# 150107_AriloTX_REV2_2_0_868MHZ_td.net
KiCad netlist of a schematic drawn in EAGLE
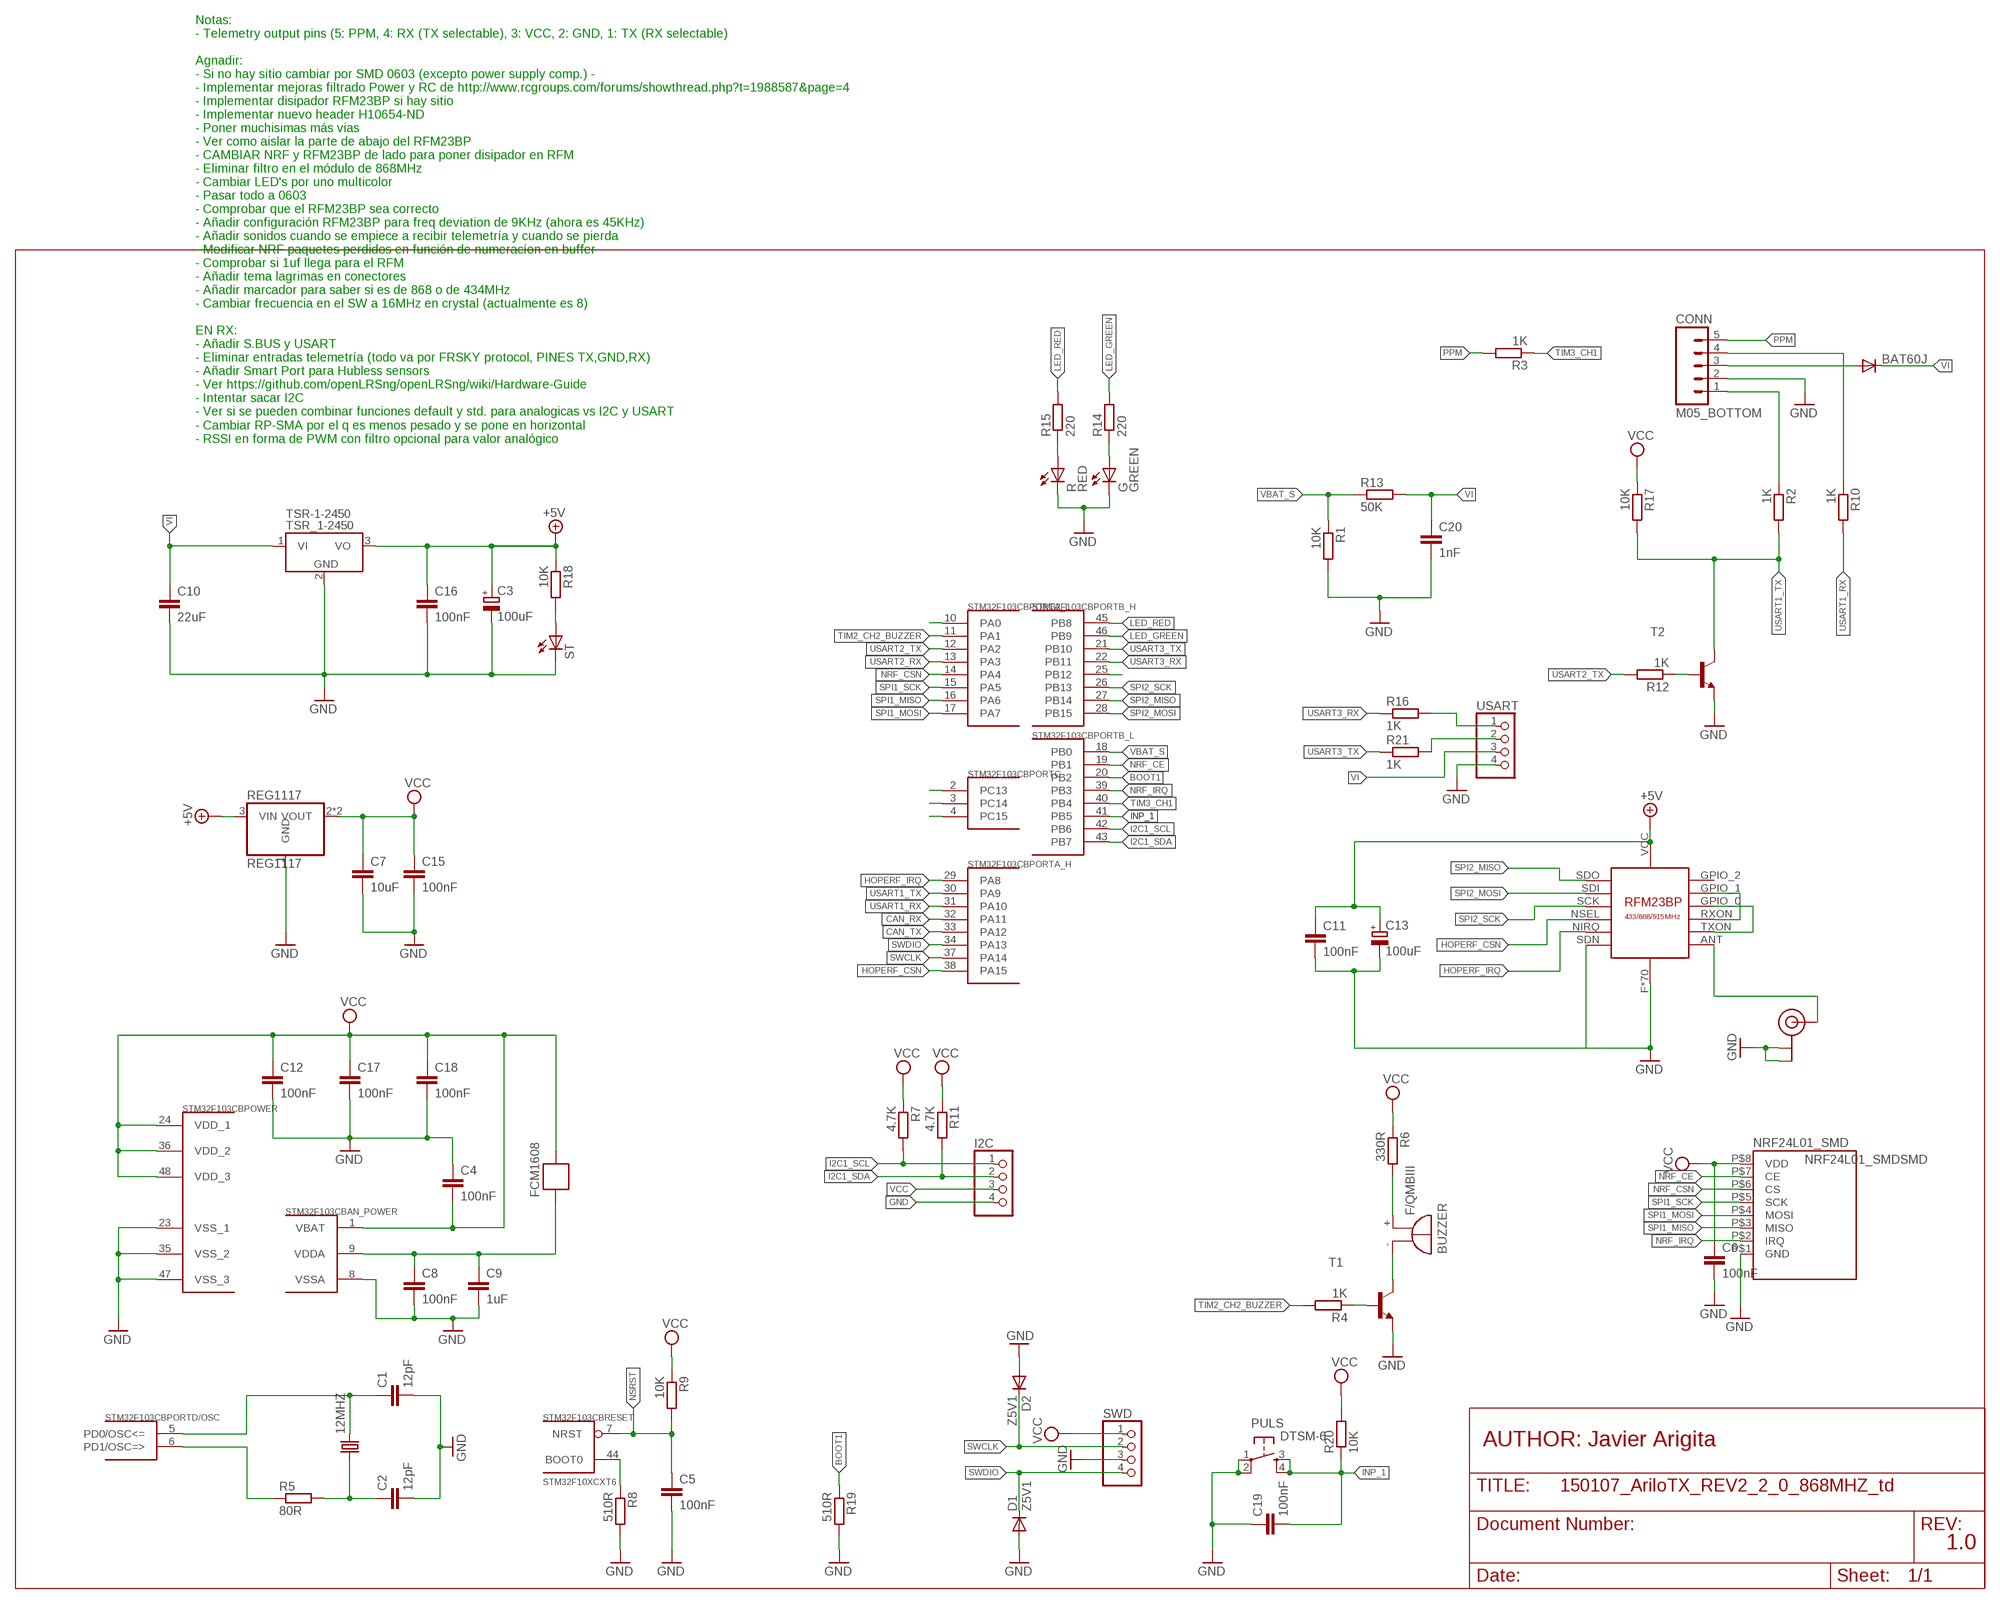
[diagram p0: schematic, sheet 1]

(export (version "E")
  (design (tool "Eeschema 10.0.6"))
  (components
    (comp (ref "12MHZ")
      (value "CRYSTAL5X3")
      (footprint "eagle-import:CRYSTAL-SMD-5X3")
      (libsource (lib "eagle-import") (part "CRYSTAL5X3"))
    )
    (comp (ref "BAT60J")
      (value "DIODE-SOD323-R")
      (footprint "eagle-import:SOD323-R")
      (libsource (lib "eagle-import") (part "DIODE-SOD323-R"))
    )
    (comp (ref "BUZZER")
      (value "F/QMBIII")
      (footprint "eagle-import:F_QMBIII")
      (libsource (lib "eagle-import") (part "F/QMBIII"))
    )
    (comp (ref "C1")
      (value "12pF")
      (footprint "eagle-import:C0603")
      (libsource (lib "eagle-import") (part "C-EUC0603"))
    )
    (comp (ref "C2")
      (value "12pF")
      (footprint "eagle-import:C0603")
      (libsource (lib "eagle-import") (part "C-EUC0603"))
    )
    (comp (ref "C3")
      (value "100uF")
      (footprint "eagle-import:SMC_B")
      (libsource (lib "eagle-import") (part "CPOL-EUSMCB"))
    )
    (comp (ref "C4")
      (value "100nF")
      (footprint "eagle-import:C0603")
      (libsource (lib "eagle-import") (part "C-EUC0603"))
    )
    (comp (ref "C5")
      (value "100nF")
      (footprint "eagle-import:C0603")
      (libsource (lib "eagle-import") (part "C-EUC0603"))
    )
    (comp (ref "C6")
      (value "100nF")
      (footprint "eagle-import:C0603")
      (libsource (lib "eagle-import") (part "C-EUC0603"))
    )
    (comp (ref "C7")
      (value "10uF")
      (footprint "eagle-import:C0805")
      (libsource (lib "eagle-import") (part "C-EUC0805"))
    )
    (comp (ref "C8")
      (value "100nF")
      (footprint "eagle-import:C0603")
      (libsource (lib "eagle-import") (part "C-EUC0603"))
    )
    (comp (ref "C9")
      (value "1uF")
      (footprint "eagle-import:C0603")
      (libsource (lib "eagle-import") (part "C-EUC0603"))
    )
    (comp (ref "C10")
      (value "22uF")
      (footprint "eagle-import:C3216")
      (libsource (lib "eagle-import") (part "resistor_C-EUC3216"))
    )
    (comp (ref "C11")
      (value "100nF")
      (footprint "eagle-import:C0603")
      (libsource (lib "eagle-import") (part "C-EUC0603"))
    )
    (comp (ref "C12")
      (value "100nF")
      (footprint "eagle-import:C0603")
      (libsource (lib "eagle-import") (part "C-EUC0603"))
    )
    (comp (ref "C13")
      (value "100uF")
      (footprint "eagle-import:SMC_B")
      (libsource (lib "eagle-import") (part "CPOL-EUSMCB"))
    )
    (comp (ref "C15")
      (value "100nF")
      (footprint "eagle-import:C0603")
      (libsource (lib "eagle-import") (part "C-EUC0603"))
    )
    (comp (ref "C16")
      (value "100nF")
      (footprint "eagle-import:C0603")
      (libsource (lib "eagle-import") (part "C-EUC0603"))
    )
    (comp (ref "C17")
      (value "100nF")
      (footprint "eagle-import:C0603")
      (libsource (lib "eagle-import") (part "C-EUC0603"))
    )
    (comp (ref "C18")
      (value "100nF")
      (footprint "eagle-import:C0603")
      (libsource (lib "eagle-import") (part "C-EUC0603"))
    )
    (comp (ref "C19")
      (value "100nF")
      (footprint "eagle-import:C0603")
      (libsource (lib "eagle-import") (part "C-EUC0603"))
    )
    (comp (ref "C20")
      (value "1nF")
      (footprint "eagle-import:C0603")
      (libsource (lib "eagle-import") (part "C-EUC0603"))
    )
    (comp (ref "CONN")
      (value "M05_BOTTOM")
      (footprint "eagle-import:M05_BOTTOM")
      (libsource (lib "eagle-import") (part "M05_BOTTOM"))
    )
    (comp (ref "D1")
      (value "Z5V1")
      (footprint "eagle-import:SOD323-R")
      (libsource (lib "eagle-import") (part "DIODE-SOD323-R"))
    )
    (comp (ref "D2")
      (value "Z5V1")
      (footprint "eagle-import:SOD323-R")
      (libsource (lib "eagle-import") (part "DIODE-SOD323-R"))
    )
    (comp (ref "FCM1608")
      (value "FERRITE-BEAD")
      (footprint "eagle-import:R0603")
      (libsource (lib "eagle-import") (part "FERRITE-BEAD"))
    )
    (comp (ref "G")
      (value "GREEN")
      (footprint "eagle-import:CHIP-LED0603")
      (libsource (lib "eagle-import") (part "LEDCHIP-LED0603"))
    )
    (comp (ref "I2C")
      (value "PINHD-1X4")
      (footprint "eagle-import:1X04")
      (libsource (lib "eagle-import") (part "PINHD-1X4"))
    )
    (comp (ref "NRF24L01_SMD")
      (value "NRF24L01_SMDSMD")
      (footprint "eagle-import:NRF24L01_SMD")
      (libsource (lib "eagle-import") (part "NRF24L01_SMDSMD"))
    )
    (comp (ref "PULS")
      (value "DTSM-6")
      (footprint "eagle-import:DTSM-6")
      (libsource (lib "eagle-import") (part "DTSM-6"))
    )
    (comp (ref "R")
      (value "RED")
      (footprint "eagle-import:CHIP-LED0603")
      (libsource (lib "eagle-import") (part "LEDCHIP-LED0603"))
    )
    (comp (ref "R1")
      (value "10K")
      (footprint "eagle-import:R0603")
      (libsource (lib "eagle-import") (part "R-EU_R0603"))
    )
    (comp (ref "R2")
      (value "1K")
      (footprint "eagle-import:R0603")
      (libsource (lib "eagle-import") (part "R-EU_R0603"))
    )
    (comp (ref "R3")
      (value "1K")
      (footprint "eagle-import:R0603")
      (libsource (lib "eagle-import") (part "R-EU_R0603"))
    )
    (comp (ref "R4")
      (value "1K")
      (footprint "eagle-import:R0603")
      (libsource (lib "eagle-import") (part "R-EU_R0603"))
    )
    (comp (ref "R5")
      (value "80R")
      (footprint "eagle-import:R0603")
      (libsource (lib "eagle-import") (part "R-EU_R0603"))
    )
    (comp (ref "R6")
      (value "330R")
      (footprint "eagle-import:R0603")
      (libsource (lib "eagle-import") (part "R-EU_R0603"))
    )
    (comp (ref "R7")
      (value "4.7K")
      (footprint "eagle-import:R0603")
      (libsource (lib "eagle-import") (part "R-EU_R0603"))
    )
    (comp (ref "R8")
      (value "510R")
      (footprint "eagle-import:R0603")
      (libsource (lib "eagle-import") (part "R-EU_R0603"))
    )
    (comp (ref "R9")
      (value "10K")
      (footprint "eagle-import:R0603")
      (libsource (lib "eagle-import") (part "R-EU_R0603"))
    )
    (comp (ref "R10")
      (value "1K")
      (footprint "eagle-import:R0603")
      (libsource (lib "eagle-import") (part "R-EU_R0603"))
    )
    (comp (ref "R11")
      (value "4.7K")
      (footprint "eagle-import:R0603")
      (libsource (lib "eagle-import") (part "R-EU_R0603"))
    )
    (comp (ref "R12")
      (value "1K")
      (footprint "eagle-import:R0603")
      (libsource (lib "eagle-import") (part "R-EU_R0603"))
    )
    (comp (ref "R13")
      (value "50K")
      (footprint "eagle-import:R0603")
      (libsource (lib "eagle-import") (part "R-EU_R0603"))
    )
    (comp (ref "R14")
      (value "220")
      (footprint "eagle-import:R0603")
      (libsource (lib "eagle-import") (part "R-EU_R0603"))
    )
    (comp (ref "R15")
      (value "220")
      (footprint "eagle-import:R0603")
      (libsource (lib "eagle-import") (part "R-EU_R0603"))
    )
    (comp (ref "R16")
      (value "1K")
      (footprint "eagle-import:R0603")
      (libsource (lib "eagle-import") (part "R-EU_R0603"))
    )
    (comp (ref "R17")
      (value "10K")
      (footprint "eagle-import:R0603")
      (libsource (lib "eagle-import") (part "R-EU_R0603"))
    )
    (comp (ref "R18")
      (value "10K")
      (footprint "eagle-import:R0603")
      (libsource (lib "eagle-import") (part "R-EU_R0603"))
    )
    (comp (ref "R19")
      (value "510R")
      (footprint "eagle-import:R0603")
      (libsource (lib "eagle-import") (part "R-EU_R0603"))
    )
    (comp (ref "R20")
      (value "10K")
      (footprint "eagle-import:R0603")
      (libsource (lib "eagle-import") (part "R-EU_R0603"))
    )
    (comp (ref "R21")
      (value "1K")
      (footprint "eagle-import:R0603")
      (libsource (lib "eagle-import") (part "R-EU_R0603"))
    )
    (comp (ref "REG1117")
      (value "REG1117")
      (footprint "eagle-import:SOT223")
      (libsource (lib "eagle-import") (part "REG1117"))
    )
    (comp (ref "ST")
      (value "LEDCHIP-LED0603")
      (footprint "eagle-import:CHIP-LED0603")
      (libsource (lib "eagle-import") (part "LEDCHIP-LED0603"))
    )
    (comp (ref "STM32F103CB")
      (value "STM32F10XCXT6")
      (footprint "eagle-import:TQFP48")
      (libsource (lib "eagle-import") (part "STM32F10XCXT6"))
    )
    (comp (ref "SWD")
      (value "PINHD-1X4")
      (footprint "eagle-import:1X04")
      (libsource (lib "eagle-import") (part "PINHD-1X4"))
    )
    (comp (ref "T1")
      (value "BC848-NPN-SOT23-BEC")
      (footprint "eagle-import:SOT23-BEC")
      (libsource (lib "eagle-import") (part "-NPN-SOT23-BECBC848"))
    )
    (comp (ref "T2")
      (value "BC848-NPN-SOT23-BEC")
      (footprint "eagle-import:SOT23-BEC")
      (libsource (lib "eagle-import") (part "-NPN-SOT23-BECBC848"))
    )
    (comp (ref "TSR-1-2450")
      (value "TSR_1-2450")
      (footprint "eagle-import:TSR-1")
      (libsource (lib "eagle-import") (part "TSR_1-2450"))
    )
    (comp (ref "U$1")
      (value "RFM23BP")
      (footprint "eagle-import:RFM23BP")
      (libsource (lib "eagle-import") (part "RFM23BP"))
    )
    (comp (ref "U.FL")
      (value "U.FL")
      (footprint "eagle-import:U.FL")
      (libsource (lib "eagle-import") (part "U.FL"))
    )
    (comp (ref "USART")
      (value "PINHD-1X4")
      (footprint "eagle-import:1X04")
      (libsource (lib "eagle-import") (part "PINHD-1X4"))
    )
  )
  (nets
    (net (code "1") (name "+5V") (class "Default")
      (node (ref "C11") (pin "1") (pinfunction "1_1") (pintype "passive"))
      (node (ref "C13") (pin "+") (pinfunction "+_+") (pintype "passive"))
      (node (ref "C16") (pin "1") (pinfunction "1_1") (pintype "passive"))
      (node (ref "C3") (pin "+") (pinfunction "+_+") (pintype "passive"))
      (node (ref "R18") (pin "1") (pinfunction "1_1") (pintype "passive"))
      (node (ref "REG1117") (pin "3") (pinfunction "VIN_3") (pintype "input"))
      (node (ref "TSR-1-2450") (pin "3") (pinfunction "VO_3") (pintype "power_in"))
      (node (ref "U$1") (pin "VCC") (pinfunction "VCC_VCC") (pintype "power_in"))
    )
    (net (code "2") (name "BOOT1") (class "Default")
      (node (ref "R19") (pin "1") (pinfunction "1_1") (pintype "passive"))
      (node (ref "STM32F103CB") (pin "20") (pinfunction "PB2_20") (pintype "bidirectional"))
    )
    (net (code "3") (name "CAN_RX") (class "Default")
      (node (ref "STM32F103CB") (pin "32") (pinfunction "PA11_32") (pintype "bidirectional"))
    )
    (net (code "4") (name "CAN_TX") (class "Default")
      (node (ref "STM32F103CB") (pin "33") (pinfunction "PA12_33") (pintype "bidirectional"))
    )
    (net (code "5") (name "GND") (class "Default")
      (node (ref "C1") (pin "2") (pinfunction "2_2") (pintype "passive"))
      (node (ref "C10") (pin "2") (pinfunction "2_2") (pintype "passive"))
      (node (ref "C11") (pin "2") (pinfunction "2_2") (pintype "passive"))
      (node (ref "C12") (pin "2") (pinfunction "2_2") (pintype "passive"))
      (node (ref "C13") (pin "-") (pinfunction "-_-") (pintype "passive"))
      (node (ref "C15") (pin "2") (pinfunction "2_2") (pintype "passive"))
      (node (ref "C16") (pin "2") (pinfunction "2_2") (pintype "passive"))
      (node (ref "C17") (pin "2") (pinfunction "2_2") (pintype "passive"))
      (node (ref "C18") (pin "2") (pinfunction "2_2") (pintype "passive"))
      (node (ref "C19") (pin "1") (pinfunction "1_1") (pintype "passive"))
      (node (ref "C2") (pin "2") (pinfunction "2_2") (pintype "passive"))
      (node (ref "C20") (pin "2") (pinfunction "2_2") (pintype "passive"))
      (node (ref "C3") (pin "-") (pinfunction "-_-") (pintype "passive"))
      (node (ref "C4") (pin "1") (pinfunction "1_1") (pintype "passive"))
      (node (ref "C5") (pin "2") (pinfunction "2_2") (pintype "passive"))
      (node (ref "C6") (pin "2") (pinfunction "2_2") (pintype "passive"))
      (node (ref "C7") (pin "2") (pinfunction "2_2") (pintype "passive"))
      (node (ref "C8") (pin "2") (pinfunction "2_2") (pintype "passive"))
      (node (ref "C9") (pin "2") (pinfunction "2_2") (pintype "passive"))
      (node (ref "CONN") (pin "2") (pinfunction "2_2") (pintype "passive"))
      (node (ref "D1") (pin "A") (pinfunction "A_A") (pintype "passive"))
      (node (ref "D2") (pin "A") (pinfunction "A_A") (pintype "passive"))
      (node (ref "G") (pin "C") (pinfunction "C_C") (pintype "passive"))
      (node (ref "I2C") (pin "4") (pinfunction "4_4") (pintype "passive"))
      (node (ref "NRF24L01_SMD") (pin "P$1") (pinfunction "GND_P$1") (pintype "power_in"))
      (node (ref "PULS") (pin "1") (pinfunction "1_1") (pintype "passive"))
      (node (ref "PULS") (pin "2") (pinfunction "2_2") (pintype "passive"))
      (node (ref "R") (pin "C") (pinfunction "C_C") (pintype "passive"))
      (node (ref "R1") (pin "2") (pinfunction "2_2") (pintype "passive"))
      (node (ref "R19") (pin "2") (pinfunction "2_2") (pintype "passive"))
      (node (ref "R8") (pin "2") (pinfunction "2_2") (pintype "passive"))
      (node (ref "REG1117") (pin "1") (pinfunction "GND_1") (pintype "power_in"))
      (node (ref "ST") (pin "C") (pinfunction "C_C") (pintype "passive"))
      (node (ref "STM32F103CB") (pin "23") (pinfunction "VSS_1_23") (pintype "power_in"))
      (node (ref "STM32F103CB") (pin "35") (pinfunction "VSS_2_35") (pintype "power_in"))
      (node (ref "STM32F103CB") (pin "47") (pinfunction "VSS_3_47") (pintype "power_in"))
      (node (ref "STM32F103CB") (pin "8") (pinfunction "VSSA_8") (pintype "power_in"))
      (node (ref "SWD") (pin "3") (pinfunction "3_3") (pintype "passive"))
      (node (ref "T1") (pin "E") (pinfunction "E_E") (pintype "passive"))
      (node (ref "T2") (pin "E") (pinfunction "E_E") (pintype "passive"))
      (node (ref "TSR-1-2450") (pin "2") (pinfunction "GND_2") (pintype "power_in"))
      (node (ref "U$1") (pin "F") (pinfunction "GND_F") (pintype "power_in"))
      (node (ref "U$1") (pin "F1") (pinfunction "GND_F1") (pintype "power_in"))
      (node (ref "U$1") (pin "F10") (pinfunction "GND_F10") (pintype "power_in"))
      (node (ref "U$1") (pin "F11") (pinfunction "GND_F11") (pintype "power_in"))
      (node (ref "U$1") (pin "F12") (pinfunction "GND_F12") (pintype "power_in"))
      (node (ref "U$1") (pin "F13") (pinfunction "GND_F13") (pintype "power_in"))
      (node (ref "U$1") (pin "F14") (pinfunction "GND_F14") (pintype "power_in"))
      (node (ref "U$1") (pin "F15") (pinfunction "GND_F15") (pintype "power_in"))
      (node (ref "U$1") (pin "F16") (pinfunction "GND_F16") (pintype "power_in"))
      (node (ref "U$1") (pin "F17") (pinfunction "GND_F17") (pintype "power_in"))
      (node (ref "U$1") (pin "F18") (pinfunction "GND_F18") (pintype "power_in"))
      (node (ref "U$1") (pin "F19") (pinfunction "GND_F19") (pintype "power_in"))
      (node (ref "U$1") (pin "F2") (pinfunction "GND_F2") (pintype "power_in"))
      (node (ref "U$1") (pin "F20") (pinfunction "GND_F20") (pintype "power_in"))
      (node (ref "U$1") (pin "F21") (pinfunction "GND_F21") (pintype "power_in"))
      (node (ref "U$1") (pin "F22") (pinfunction "GND_F22") (pintype "power_in"))
      (node (ref "U$1") (pin "F23") (pinfunction "GND_F23") (pintype "power_in"))
      (node (ref "U$1") (pin "F24") (pinfunction "GND_F24") (pintype "power_in"))
      (node (ref "U$1") (pin "F25") (pinfunction "GND_F25") (pintype "power_in"))
      (node (ref "U$1") (pin "F26") (pinfunction "GND_F26") (pintype "power_in"))
      (node (ref "U$1") (pin "F27") (pinfunction "GND_F27") (pintype "power_in"))
      (node (ref "U$1") (pin "F28") (pinfunction "GND_F28") (pintype "power_in"))
      (node (ref "U$1") (pin "F29") (pinfunction "GND_F29") (pintype "power_in"))
      (node (ref "U$1") (pin "F3") (pinfunction "GND_F3") (pintype "power_in"))
      (node (ref "U$1") (pin "F30") (pinfunction "GND_F30") (pintype "power_in"))
      (node (ref "U$1") (pin "F31") (pinfunction "GND_F31") (pintype "power_in"))
      (node (ref "U$1") (pin "F32") (pinfunction "GND_F32") (pintype "power_in"))
      (node (ref "U$1") (pin "F33") (pinfunction "GND_F33") (pintype "power_in"))
      (node (ref "U$1") (pin "F34") (pinfunction "GND_F34") (pintype "power_in"))
      (node (ref "U$1") (pin "F35") (pinfunction "GND_F35") (pintype "power_in"))
      (node (ref "U$1") (pin "F36") (pinfunction "GND_F36") (pintype "power_in"))
      (node (ref "U$1") (pin "F37") (pinfunction "GND_F37") (pintype "power_in"))
      (node (ref "U$1") (pin "F38") (pinfunction "GND_F38") (pintype "power_in"))
      (node (ref "U$1") (pin "F39") (pinfunction "GND_F39") (pintype "power_in"))
      (node (ref "U$1") (pin "F4") (pinfunction "GND_F4") (pintype "power_in"))
      (node (ref "U$1") (pin "F40") (pinfunction "GND_F40") (pintype "power_in"))
      (node (ref "U$1") (pin "F41") (pinfunction "GND_F41") (pintype "power_in"))
      (node (ref "U$1") (pin "F42") (pinfunction "GND_F42") (pintype "power_in"))
      (node (ref "U$1") (pin "F43") (pinfunction "GND_F43") (pintype "power_in"))
      (node (ref "U$1") (pin "F44") (pinfunction "GND_F44") (pintype "power_in"))
      (node (ref "U$1") (pin "F45") (pinfunction "GND_F45") (pintype "power_in"))
      (node (ref "U$1") (pin "F46") (pinfunction "GND_F46") (pintype "power_in"))
      (node (ref "U$1") (pin "F47") (pinfunction "GND_F47") (pintype "power_in"))
      (node (ref "U$1") (pin "F48") (pinfunction "GND_F48") (pintype "power_in"))
      (node (ref "U$1") (pin "F49") (pinfunction "GND_F49") (pintype "power_in"))
      (node (ref "U$1") (pin "F5") (pinfunction "GND_F5") (pintype "power_in"))
      (node (ref "U$1") (pin "F50") (pinfunction "GND_F50") (pintype "power_in"))
      (node (ref "U$1") (pin "F51") (pinfunction "GND_F51") (pintype "power_in"))
      (node (ref "U$1") (pin "F52") (pinfunction "GND_F52") (pintype "power_in"))
      (node (ref "U$1") (pin "F53") (pinfunction "GND_F53") (pintype "power_in"))
      (node (ref "U$1") (pin "F54") (pinfunction "GND_F54") (pintype "power_in"))
      (node (ref "U$1") (pin "F55") (pinfunction "GND_F55") (pintype "power_in"))
      (node (ref "U$1") (pin "F56") (pinfunction "GND_F56") (pintype "power_in"))
      (node (ref "U$1") (pin "F57") (pinfunction "GND_F57") (pintype "power_in"))
      (node (ref "U$1") (pin "F58") (pinfunction "GND_F58") (pintype "power_in"))
      (node (ref "U$1") (pin "F59") (pinfunction "GND_F59") (pintype "power_in"))
      (node (ref "U$1") (pin "F6") (pinfunction "GND_F6") (pintype "power_in"))
      (node (ref "U$1") (pin "F60") (pinfunction "GND_F60") (pintype "power_in"))
      (node (ref "U$1") (pin "F61") (pinfunction "GND_F61") (pintype "power_in"))
      (node (ref "U$1") (pin "F62") (pinfunction "GND_F62") (pintype "power_in"))
      (node (ref "U$1") (pin "F63") (pinfunction "GND_F63") (pintype "power_in"))
      (node (ref "U$1") (pin "F64") (pinfunction "GND_F64") (pintype "power_in"))
      (node (ref "U$1") (pin "F65") (pinfunction "GND_F65") (pintype "power_in"))
      (node (ref "U$1") (pin "F7") (pinfunction "GND_F7") (pintype "power_in"))
      (node (ref "U$1") (pin "F8") (pinfunction "GND_F8") (pintype "power_in"))
      (node (ref "U$1") (pin "F9") (pinfunction "GND_F9") (pintype "power_in"))
      (node (ref "U$1") (pin "GND1") (pinfunction "GND_GND1") (pintype "power_in"))
      (node (ref "U$1") (pin "GND2") (pinfunction "GND_GND2") (pintype "power_in"))
      (node (ref "U$1") (pin "GND3") (pinfunction "GND_GND3") (pintype "power_in"))
      (node (ref "U$1") (pin "GND_HEAT") (pinfunction "GND_GND_HEAT") (pintype "power_in"))
      (node (ref "U$1") (pin "SDN") (pinfunction "SDN_SDN") (pintype "bidirectional"))
      (node (ref "U.FL") (pin "P$1") (pinfunction "GND_P$1") (pintype "bidirectional"))
      (node (ref "U.FL") (pin "P$2") (pinfunction "GND_P$2") (pintype "bidirectional"))
      (node (ref "USART") (pin "4") (pinfunction "4_4") (pintype "passive"))
    )
    (net (code "6") (name "HOPERF_CSN") (class "Default")
      (node (ref "STM32F103CB") (pin "38") (pinfunction "PA15_38") (pintype "bidirectional"))
      (node (ref "U$1") (pin "NSEL") (pinfunction "NSEL_NSEL") (pintype "bidirectional"))
    )
    (net (code "7") (name "HOPERF_IRQ") (class "Default")
      (node (ref "STM32F103CB") (pin "29") (pinfunction "PA8_29") (pintype "bidirectional"))
      (node (ref "U$1") (pin "NIRQ") (pinfunction "NIRQ_NIRQ") (pintype "bidirectional"))
    )
    (net (code "8") (name "I2C1_SCL") (class "Default")
      (node (ref "I2C") (pin "1") (pinfunction "1_1") (pintype "passive"))
      (node (ref "R7") (pin "2") (pinfunction "2_2") (pintype "passive"))
      (node (ref "STM32F103CB") (pin "42") (pinfunction "PB6_42") (pintype "bidirectional"))
    )
    (net (code "9") (name "I2C1_SDA") (class "Default")
      (node (ref "I2C") (pin "2") (pinfunction "2_2") (pintype "passive"))
      (node (ref "R11") (pin "2") (pinfunction "2_2") (pintype "passive"))
      (node (ref "STM32F103CB") (pin "43") (pinfunction "PB7_43") (pintype "bidirectional"))
    )
    (net (code "10") (name "INP_1") (class "Default")
      (node (ref "C19") (pin "2") (pinfunction "2_2") (pintype "passive"))
      (node (ref "PULS") (pin "3") (pinfunction "3_3") (pintype "passive"))
      (node (ref "PULS") (pin "4") (pinfunction "4_4") (pintype "passive"))
      (node (ref "R20") (pin "1") (pinfunction "1_1") (pintype "passive"))
      (node (ref "STM32F103CB") (pin "41") (pinfunction "PB5_41") (pintype "bidirectional"))
    )
    (net (code "11") (name "LED_GREEN") (class "Default")
      (node (ref "R14") (pin "2") (pinfunction "2_2") (pintype "passive"))
      (node (ref "STM32F103CB") (pin "46") (pinfunction "PB9_46") (pintype "bidirectional"))
    )
    (net (code "12") (name "LED_RED") (class "Default")
      (node (ref "R15") (pin "2") (pinfunction "2_2") (pintype "passive"))
      (node (ref "STM32F103CB") (pin "45") (pinfunction "PB8_45") (pintype "bidirectional"))
    )
    (net (code "13") (name "NRF_CE") (class "Default")
      (node (ref "NRF24L01_SMD") (pin "P$7") (pinfunction "CE_P$7") (pintype "input"))
      (node (ref "STM32F103CB") (pin "19") (pinfunction "PB1_19") (pintype "bidirectional"))
    )
    (net (code "14") (name "NRF_CSN") (class "Default")
      (node (ref "NRF24L01_SMD") (pin "P$6") (pinfunction "CS_P$6") (pintype "input"))
      (node (ref "STM32F103CB") (pin "14") (pinfunction "PA4_14") (pintype "bidirectional"))
    )
    (net (code "15") (name "NRF_IRQ") (class "Default")
      (node (ref "NRF24L01_SMD") (pin "P$2") (pinfunction "IRQ_P$2") (pintype "output"))
      (node (ref "STM32F103CB") (pin "39") (pinfunction "PB3_39") (pintype "bidirectional"))
    )
    (net (code "16") (name "NSRST") (class "Default")
      (node (ref "C5") (pin "1") (pinfunction "1_1") (pintype "passive"))
      (node (ref "R9") (pin "2") (pinfunction "2_2") (pintype "passive"))
      (node (ref "STM32F103CB") (pin "7") (pinfunction "NRST_7") (pintype "input"))
    )
    (net (code "17") (name "Net-(12MHZ-2)") (class "Default")
      (node (ref "12MHZ") (pin "3") (pinfunction "2_3") (pintype "passive"))
      (node (ref "C1") (pin "1") (pinfunction "1_1") (pintype "passive"))
      (node (ref "STM32F103CB") (pin "5") (pinfunction "PD0/OSC<=_5") (pintype "bidirectional"))
    )
    (net (code "18") (name "Net-(12MHZ-Pad1)") (class "Default")
      (node (ref "12MHZ") (pin "1") (pinfunction "1_1") (pintype "passive"))
      (node (ref "C2") (pin "1") (pinfunction "1_1") (pintype "passive"))
      (node (ref "R5") (pin "2") (pinfunction "2_2") (pintype "passive"))
    )
    (net (code "19") (name "Net-(BAT60J-PadA)") (class "Default")
      (node (ref "BAT60J") (pin "A") (pinfunction "A_A") (pintype "passive"))
      (node (ref "CONN") (pin "3") (pinfunction "3_3") (pintype "passive"))
    )
    (net (code "20") (name "Net-(BUZZER-+)") (class "Default")
      (node (ref "BUZZER") (pin "-") (pinfunction "+_-") (pintype "passive"))
      (node (ref "T1") (pin "C") (pinfunction "C_C") (pintype "passive"))
    )
    (net (code "21") (name "Net-(BUZZER--)") (class "Default")
      (node (ref "BUZZER") (pin "+") (pinfunction "-_+") (pintype "passive"))
      (node (ref "R6") (pin "2") (pinfunction "2_2") (pintype "passive"))
    )
    (net (code "22") (name "Net-(CONN-Pad1)") (class "Default")
      (node (ref "CONN") (pin "1") (pinfunction "1_1") (pintype "passive"))
      (node (ref "R2") (pin "1") (pinfunction "1_1") (pintype "passive"))
    )
    (net (code "23") (name "Net-(CONN-Pad4)") (class "Default")
      (node (ref "CONN") (pin "4") (pinfunction "4_4") (pintype "passive"))
      (node (ref "R10") (pin "1") (pinfunction "1_1") (pintype "passive"))
    )
    (net (code "24") (name "Net-(FCM1608-P$2)") (class "Default")
      (node (ref "C8") (pin "1") (pinfunction "1_1") (pintype "passive"))
      (node (ref "C9") (pin "1") (pinfunction "1_1") (pintype "passive"))
      (node (ref "FCM1608") (pin "2") (pinfunction "P$2_2") (pintype "bidirectional"))
      (node (ref "STM32F103CB") (pin "9") (pinfunction "VDDA_9") (pintype "power_in"))
    )
    (net (code "25") (name "Net-(G-PadA)") (class "Default")
      (node (ref "G") (pin "A") (pinfunction "A_A") (pintype "passive"))
      (node (ref "R14") (pin "1") (pinfunction "1_1") (pintype "passive"))
    )
    (net (code "26") (name "Net-(R-PadA)") (class "Default")
      (node (ref "R") (pin "A") (pinfunction "A_A") (pintype "passive"))
      (node (ref "R15") (pin "1") (pinfunction "1_1") (pintype "passive"))
    )
    (net (code "27") (name "Net-(R4-Pad1)") (class "Default")
      (node (ref "R4") (pin "1") (pinfunction "1_1") (pintype "passive"))
      (node (ref "T1") (pin "B") (pinfunction "B_B") (pintype "passive"))
    )
    (net (code "28") (name "Net-(R12-Pad1)") (class "Default")
      (node (ref "R12") (pin "1") (pinfunction "1_1") (pintype "passive"))
      (node (ref "T2") (pin "B") (pinfunction "B_B") (pintype "passive"))
    )
    (net (code "29") (name "Net-(R16-Pad2)") (class "Default")
      (node (ref "R16") (pin "2") (pinfunction "2_2") (pintype "passive"))
      (node (ref "USART") (pin "1") (pinfunction "1_1") (pintype "passive"))
    )
    (net (code "30") (name "Net-(R18-Pad2)") (class "Default")
      (node (ref "R18") (pin "2") (pinfunction "2_2") (pintype "passive"))
      (node (ref "ST") (pin "A") (pinfunction "A_A") (pintype "passive"))
    )
    (net (code "31") (name "Net-(R21-Pad2)") (class "Default")
      (node (ref "R21") (pin "2") (pinfunction "2_2") (pintype "passive"))
      (node (ref "USART") (pin "2") (pinfunction "2_2") (pintype "passive"))
    )
    (net (code "32") (name "Net-(STM32F103CBG-PD1{slash}OSC=>)") (class "Default")
      (node (ref "R5") (pin "1") (pinfunction "1_1") (pintype "passive"))
      (node (ref "STM32F103CB") (pin "6") (pinfunction "PD1/OSC=>_6") (pintype "bidirectional"))
    )
    (net (code "33") (name "Net-(STM32F103CBI-BOOT0)") (class "Default")
      (node (ref "R8") (pin "1") (pinfunction "1_1") (pintype "passive"))
      (node (ref "STM32F103CB") (pin "44") (pinfunction "BOOT0_44") (pintype "input"))
    )
    (net (code "34") (name "Net-(U$1-PadGPIO_0)") (class "Default")
      (node (ref "U$1") (pin "GPIO_0") (pinfunction "GPIO_0_GPIO_0") (pintype "bidirectional"))
      (node (ref "U$1") (pin "TXON") (pinfunction "TXON_TXON") (pintype "bidirectional"))
    )
    (net (code "35") (name "Net-(U$1-PadGPIO_1)") (class "Default")
      (node (ref "U$1") (pin "GPIO_1") (pinfunction "GPIO_1_GPIO_1") (pintype "bidirectional"))
      (node (ref "U$1") (pin "RXON") (pinfunction "RXON_RXON") (pintype "bidirectional"))
    )
    (net (code "36") (name "Net-(U.FL-SIGNAL)") (class "Default")
      (node (ref "U$1") (pin "ANT") (pinfunction "ANT_ANT") (pintype "bidirectional"))
      (node (ref "U.FL") (pin "P$3") (pinfunction "SIGNAL_P$3") (pintype "bidirectional"))
    )
    (net (code "37") (name "PPM") (class "Default")
      (node (ref "CONN") (pin "5") (pinfunction "5_5") (pintype "passive"))
      (node (ref "R3") (pin "2") (pinfunction "2_2") (pintype "passive"))
    )
    (net (code "38") (name "SPI1_MISO") (class "Default")
      (node (ref "NRF24L01_SMD") (pin "P$3") (pinfunction "MISO_P$3") (pintype "output"))
      (node (ref "STM32F103CB") (pin "16") (pinfunction "PA6_16") (pintype "bidirectional"))
    )
    (net (code "39") (name "SPI1_MOSI") (class "Default")
      (node (ref "NRF24L01_SMD") (pin "P$4") (pinfunction "MOSI_P$4") (pintype "input"))
      (node (ref "STM32F103CB") (pin "17") (pinfunction "PA7_17") (pintype "bidirectional"))
    )
    (net (code "40") (name "SPI1_SCK") (class "Default")
      (node (ref "NRF24L01_SMD") (pin "P$5") (pinfunction "SCK_P$5") (pintype "input"))
      (node (ref "STM32F103CB") (pin "15") (pinfunction "PA5_15") (pintype "bidirectional"))
    )
    (net (code "41") (name "SPI2_MISO") (class "Default")
      (node (ref "STM32F103CB") (pin "27") (pinfunction "PB14_27") (pintype "bidirectional"))
      (node (ref "U$1") (pin "SDO") (pinfunction "SDO_SDO") (pintype "bidirectional"))
    )
    (net (code "42") (name "SPI2_MOSI") (class "Default")
      (node (ref "STM32F103CB") (pin "28") (pinfunction "PB15_28") (pintype "bidirectional"))
      (node (ref "U$1") (pin "SDI") (pinfunction "SDI_SDI") (pintype "bidirectional"))
    )
    (net (code "43") (name "SPI2_SCK") (class "Default")
      (node (ref "STM32F103CB") (pin "26") (pinfunction "PB13_26") (pintype "bidirectional"))
      (node (ref "U$1") (pin "SCK") (pinfunction "SCK_SCK") (pintype "bidirectional"))
    )
    (net (code "44") (name "SWCLK") (class "Default")
      (node (ref "D2") (pin "C") (pinfunction "C_C") (pintype "passive"))
      (node (ref "STM32F103CB") (pin "37") (pinfunction "PA14_37") (pintype "bidirectional"))
      (node (ref "SWD") (pin "2") (pinfunction "2_2") (pintype "passive"))
    )
    (net (code "45") (name "SWDIO") (class "Default")
      (node (ref "D1") (pin "C") (pinfunction "C_C") (pintype "passive"))
      (node (ref "STM32F103CB") (pin "34") (pinfunction "PA13_34") (pintype "bidirectional"))
      (node (ref "SWD") (pin "4") (pinfunction "4_4") (pintype "passive"))
    )
    (net (code "46") (name "TIM2_CH2_BUZZER") (class "Default")
      (node (ref "R4") (pin "2") (pinfunction "2_2") (pintype "passive"))
      (node (ref "STM32F103CB") (pin "11") (pinfunction "PA1_11") (pintype "bidirectional"))
    )
    (net (code "47") (name "TIM3_CH1") (class "Default")
      (node (ref "R3") (pin "1") (pinfunction "1_1") (pintype "passive"))
      (node (ref "STM32F103CB") (pin "40") (pinfunction "PB4_40") (pintype "bidirectional"))
    )
    (net (code "48") (name "USART1_RX") (class "Default")
      (node (ref "R10") (pin "2") (pinfunction "2_2") (pintype "passive"))
      (node (ref "STM32F103CB") (pin "31") (pinfunction "PA10_31") (pintype "bidirectional"))
    )
    (net (code "49") (name "USART1_TX") (class "Default")
      (node (ref "R17") (pin "2") (pinfunction "2_2") (pintype "passive"))
      (node (ref "R2") (pin "2") (pinfunction "2_2") (pintype "passive"))
      (node (ref "STM32F103CB") (pin "30") (pinfunction "PA9_30") (pintype "bidirectional"))
      (node (ref "T2") (pin "C") (pinfunction "C_C") (pintype "passive"))
    )
    (net (code "50") (name "USART2_RX") (class "Default")
      (node (ref "STM32F103CB") (pin "13") (pinfunction "PA3_13") (pintype "bidirectional"))
    )
    (net (code "51") (name "USART2_TX") (class "Default")
      (node (ref "R12") (pin "2") (pinfunction "2_2") (pintype "passive"))
      (node (ref "STM32F103CB") (pin "12") (pinfunction "PA2_12") (pintype "bidirectional"))
    )
    (net (code "52") (name "USART3_RX") (class "Default")
      (node (ref "R16") (pin "1") (pinfunction "1_1") (pintype "passive"))
      (node (ref "STM32F103CB") (pin "22") (pinfunction "PB11_22") (pintype "bidirectional"))
    )
    (net (code "53") (name "USART3_TX") (class "Default")
      (node (ref "R21") (pin "1") (pinfunction "1_1") (pintype "passive"))
      (node (ref "STM32F103CB") (pin "21") (pinfunction "PB10_21") (pintype "bidirectional"))
    )
    (net (code "54") (name "VBAT_S") (class "Default")
      (node (ref "R1") (pin "1") (pinfunction "1_1") (pintype "passive"))
      (node (ref "R13") (pin "1") (pinfunction "1_1") (pintype "passive"))
      (node (ref "STM32F103CB") (pin "18") (pinfunction "PB0_18") (pintype "bidirectional"))
    )
    (net (code "55") (name "VCC") (class "Default")
      (node (ref "C12") (pin "1") (pinfunction "1_1") (pintype "passive"))
      (node (ref "C15") (pin "1") (pinfunction "1_1") (pintype "passive"))
      (node (ref "C17") (pin "1") (pinfunction "1_1") (pintype "passive"))
      (node (ref "C18") (pin "1") (pinfunction "1_1") (pintype "passive"))
      (node (ref "C4") (pin "2") (pinfunction "2_2") (pintype "passive"))
      (node (ref "C6") (pin "1") (pinfunction "1_1") (pintype "passive"))
      (node (ref "C7") (pin "1") (pinfunction "1_1") (pintype "passive"))
      (node (ref "FCM1608") (pin "1") (pinfunction "P$1_1") (pintype "bidirectional"))
      (node (ref "I2C") (pin "3") (pinfunction "3_3") (pintype "passive"))
      (node (ref "NRF24L01_SMD") (pin "P$8") (pinfunction "VDD_P$8") (pintype "bidirectional"))
      (node (ref "R11") (pin "1") (pinfunction "1_1") (pintype "passive"))
      (node (ref "R17") (pin "1") (pinfunction "1_1") (pintype "passive"))
      (node (ref "R20") (pin "2") (pinfunction "2_2") (pintype "passive"))
      (node (ref "R6") (pin "1") (pinfunction "1_1") (pintype "passive"))
      (node (ref "R7") (pin "1") (pinfunction "1_1") (pintype "passive"))
      (node (ref "R9") (pin "1") (pinfunction "1_1") (pintype "passive"))
      (node (ref "REG1117") (pin "2") (pinfunction "VOUT_2") (pintype "power_in"))
      (node (ref "REG1117") (pin "4") (pinfunction "VOUT_4") (pintype "power_in"))
      (node (ref "STM32F103CB") (pin "1") (pinfunction "VBAT_1") (pintype "power_in"))
      (node (ref "STM32F103CB") (pin "24") (pinfunction "VDD_1_24") (pintype "power_in"))
      (node (ref "STM32F103CB") (pin "36") (pinfunction "VDD_2_36") (pintype "power_in"))
      (node (ref "STM32F103CB") (pin "48") (pinfunction "VDD_3_48") (pintype "power_in"))
      (node (ref "SWD") (pin "1") (pinfunction "1_1") (pintype "passive"))
    )
    (net (code "56") (name "VI") (class "Default")
      (node (ref "BAT60J") (pin "C") (pinfunction "C_C") (pintype "passive"))
      (node (ref "C10") (pin "1") (pinfunction "1_1") (pintype "passive"))
      (node (ref "C20") (pin "1") (pinfunction "1_1") (pintype "passive"))
      (node (ref "R13") (pin "2") (pinfunction "2_2") (pintype "passive"))
      (node (ref "TSR-1-2450") (pin "1") (pinfunction "VI_1") (pintype "power_in"))
      (node (ref "USART") (pin "3") (pinfunction "3_3") (pintype "passive"))
    )
    (net (code "57") (name "unconnected-(STM32F103CBC-PA0-Pad10)") (class "Default")
      (node (ref "STM32F103CB") (pin "10") (pinfunction "PA0_10") (pintype "bidirectional"))
    )
    (net (code "58") (name "unconnected-(STM32F103CBD-PB12-Pad25)") (class "Default")
      (node (ref "STM32F103CB") (pin "25") (pinfunction "PB12_25") (pintype "bidirectional"))
    )
    (net (code "59") (name "unconnected-(STM32F103CBF-PC13-Pad2)") (class "Default")
      (node (ref "STM32F103CB") (pin "2") (pinfunction "PC13_2") (pintype "bidirectional"))
    )
    (net (code "60") (name "unconnected-(STM32F103CBF-PC14-Pad3)") (class "Default")
      (node (ref "STM32F103CB") (pin "3") (pinfunction "PC14_3") (pintype "bidirectional"))
    )
    (net (code "61") (name "unconnected-(STM32F103CBF-PC15-Pad4)") (class "Default")
      (node (ref "STM32F103CB") (pin "4") (pinfunction "PC15_4") (pintype "bidirectional"))
    )
    (net (code "62") (name "unconnected-(U$1-PadGPIO_2)") (class "Default")
      (node (ref "U$1") (pin "GPIO_2") (pinfunction "GPIO_2_GPIO_2") (pintype "bidirectional"))
    )
  )
)
